# OMT_I2C_Int.net
KiCad netlist of a schematic drawn in Altium Designer
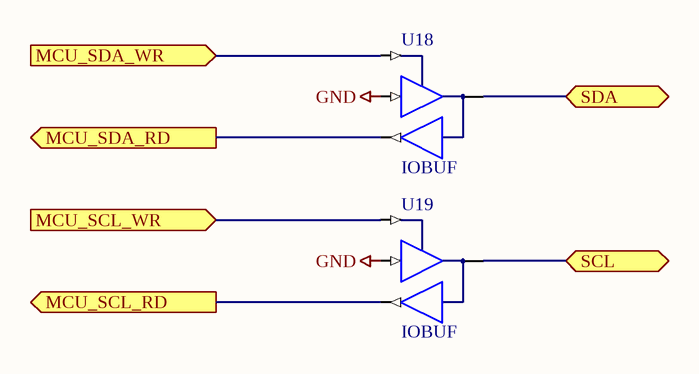
[diagram p0: OMT_I2C_Int.SchDoc]

(export (version "E")
  (design (tool "Eeschema 10.0.6"))
  (components
    (comp (ref "U18")
      (value "IOBUF")
      (description "Input/Output Buffer")
      (fields (field (name "PUBLISHER") "Altium Limited"))
      (libsource (lib "FPGA Generic") (part "IOBUF"))
    )
    (comp (ref "U19")
      (value "IOBUF")
      (description "Input/Output Buffer")
      (fields (field (name "PUBLISHER") "Altium Limited"))
      (libsource (lib "FPGA Generic") (part "IOBUF"))
    )
  )
  (nets
    (net (code "1") (name "/MCU_SCL_RD") (class "Default")
      (node (ref "U19") (pin "O") (pinfunction "O_O") (pintype "output"))
    )
    (net (code "2") (name "/MCU_SCL_WR") (class "Default")
      (node (ref "U19") (pin "T") (pinfunction "T_T") (pintype "input"))
    )
    (net (code "3") (name "/MCU_SDA_RD") (class "Default")
      (node (ref "U18") (pin "O") (pinfunction "O_O") (pintype "output"))
    )
    (net (code "4") (name "/MCU_SDA_WR") (class "Default")
      (node (ref "U18") (pin "T") (pinfunction "T_T") (pintype "input"))
    )
    (net (code "5") (name "/SCL") (class "Default")
      (node (ref "U19") (pin "IO") (pinfunction "IO_IO") (pintype "bidirectional"))
    )
    (net (code "6") (name "/SDA") (class "Default")
      (node (ref "U18") (pin "IO") (pinfunction "IO_IO") (pintype "bidirectional"))
    )
    (net (code "7") (name "GND") (class "Default")
      (node (ref "U18") (pin "I") (pinfunction "I_I") (pintype "input"))
      (node (ref "U19") (pin "I") (pinfunction "I_I") (pintype "input"))
    )
  )
)
